# core.net
KiCad netlist of a schematic drawn in EAGLE
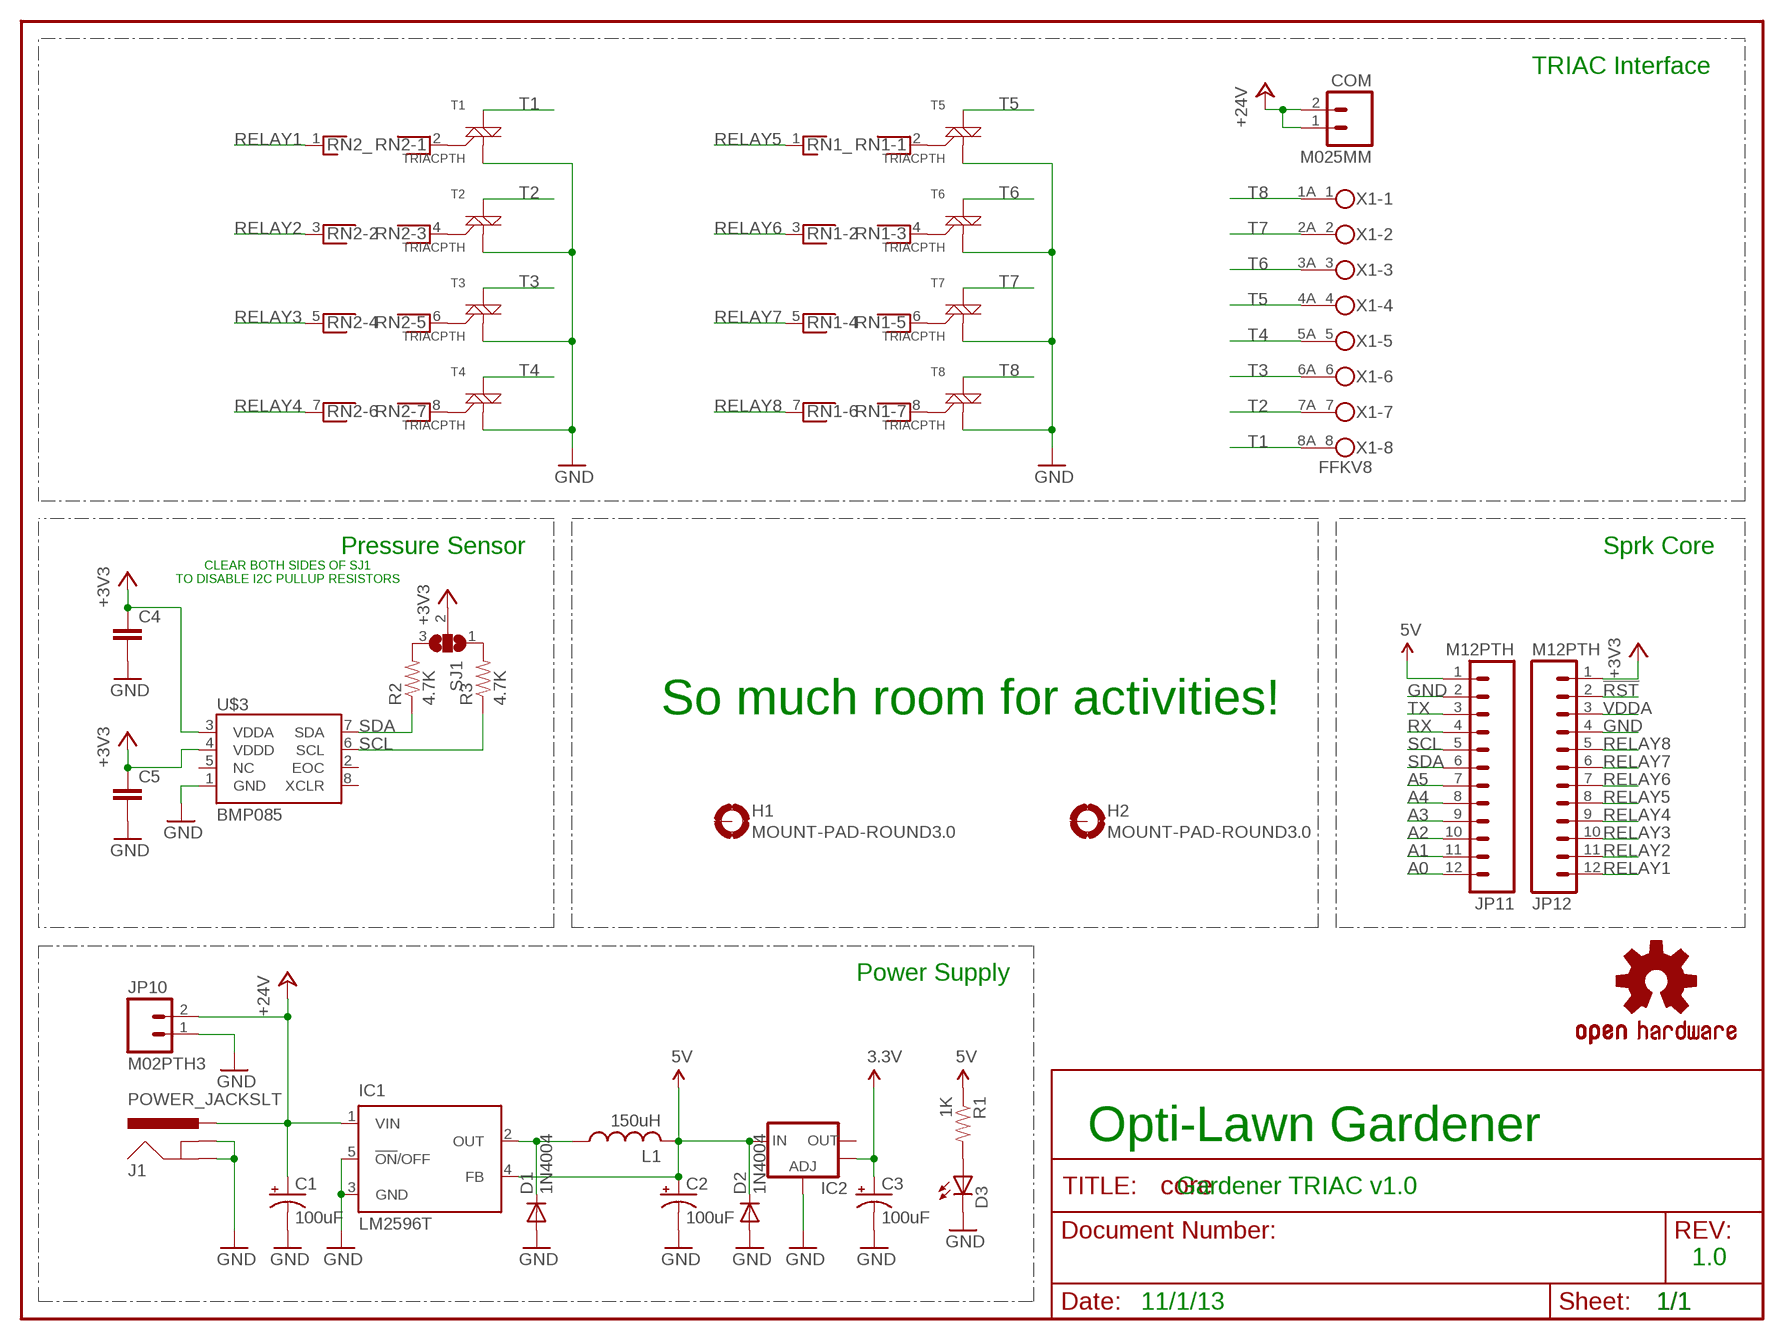
[diagram p0: schematic, sheet 1]

(export (version "E")
  (design (tool "Eeschema 10.0.6"))
  (components
    (comp (ref "C1")
      (value "100uF")
      (footprint "eagle-import:CPOL-RADIAL-100UF-25V")
      (fields (field (name "MPN") "10NA100MEFC6.3X11"))
      (libsource (lib "eagle-import") (part "CAP_POLPTH1"))
    )
    (comp (ref "C2")
      (value "100uF")
      (footprint "eagle-import:CPOL-RADIAL-100UF-25V")
      (fields (field (name "MPN") "10NA100MEFC6.3X11"))
      (libsource (lib "eagle-import") (part "CAP_POLPTH1"))
    )
    (comp (ref "C3")
      (value "100uF")
      (footprint "eagle-import:CPOL-RADIAL-100UF-25V")
      (fields (field (name "MPN") "10NA100MEFC6.3X11"))
      (libsource (lib "eagle-import") (part "CAP_POLPTH1"))
    )
    (comp (ref "C4")
      (value "CAP0402-CAP")
      (footprint "eagle-import:0402-CAP")
      (libsource (lib "eagle-import") (part "CAP0402-CAP"))
    )
    (comp (ref "C5")
      (value "CAP0402-CAP")
      (footprint "eagle-import:0402-CAP")
      (libsource (lib "eagle-import") (part "CAP0402-CAP"))
    )
    (comp (ref "COM")
      (value "M025MM")
      (footprint "eagle-import:SCREWTERMINAL-5MM-2")
      (fields (field (name "MPN") "724"))
      (libsource (lib "eagle-import") (part "M025MM"))
    )
    (comp (ref "D1")
      (value "1N4004")
      (footprint "eagle-import:DO41-10")
      (fields (field (name "MF") "FAIRCHILD SEMICONDUCTOR"))
      (libsource (lib "eagle-import") (part "1N4004"))
    )
    (comp (ref "D2")
      (value "1N4004")
      (footprint "eagle-import:DO41-10")
      (fields (field (name "MF") "FAIRCHILD SEMICONDUCTOR"))
      (libsource (lib "eagle-import") (part "1N4004"))
    )
    (comp (ref "D3")
      (value "LED3MM")
      (footprint "eagle-import:LED3MM")
      (fields (field (name "MPN") "L-710A8CB/1GD"))
      (libsource (lib "eagle-import") (part "LED3MM"))
    )
    (comp (ref "H1")
      (value "MOUNT-PAD-ROUND3.0")
      (footprint "eagle-import:3,0-PAD")
      (libsource (lib "eagle-import") (part "MOUNT-PAD-ROUND3.0"))
    )
    (comp (ref "H2")
      (value "MOUNT-PAD-ROUND3.0")
      (footprint "eagle-import:3,0-PAD")
      (libsource (lib "eagle-import") (part "MOUNT-PAD-ROUND3.0"))
    )
    (comp (ref "IC1")
      (value "LM2596T")
      (footprint "eagle-import:T05D")
      (fields
        (field (name "MPN") "LM2596T-ADJ/LF02")
        (field (name "MF") "NATIONAL SEMICONDUCTOR")
        (field (name "MPN_1") "LM2596T-5.0/NOPB")
        (field (name "OC_NEWARK") "41K3851")
      )
      (libsource (lib "eagle-import") (part "LM2596T"))
    )
    (comp (ref "IC2")
      (value "V_REG_LM1117SOT223")
      (footprint "eagle-import:SOT223")
      (fields (field (name "MPN") "LM1117MPX-3.3/NOPB"))
      (libsource (lib "eagle-import") (part "V_REG_LM1117SOT223"))
    )
    (comp (ref "J1")
      (value "POWER_JACKSLT")
      (footprint "eagle-import:POWER_JACK_SLOT")
      (libsource (lib "eagle-import") (part "POWER_JACKSLT"))
    )
    (comp (ref "JP10")
      (value "M02PTH3")
      (footprint "eagle-import:1X02_LONGPADS")
      (libsource (lib "eagle-import") (part "M02PTH3"))
    )
    (comp (ref "JP11")
      (value "M12PTH")
      (footprint "eagle-import:1X12-SMALL-PADS")
      (libsource (lib "eagle-import") (part "M12PTH"))
    )
    (comp (ref "JP12")
      (value "M12PTH")
      (footprint "eagle-import:1X12-SMALL-PADS")
      (libsource (lib "eagle-import") (part "M12PTH"))
    )
    (comp (ref "L1")
      (value "150uH")
      (footprint "eagle-import:6000")
      (fields (field (name "MPN") "RLB9012-151KL"))
      (libsource (lib "eagle-import") (part "L"))
    )
    (comp (ref "LOGO2")
      (value "OSHW-LOGOL")
      (footprint "eagle-import:OSHW-LOGO-L")
      (libsource (lib "eagle-import") (part "OSHW-LOGOL"))
    )
    (comp (ref "R1")
      (value "1K")
      (footprint "eagle-import:AXIAL-0.3")
      (fields (field (name "MF") "FARNELL") (field (name "MPN") "MCF 1W 1K"))
      (libsource (lib "eagle-import") (part "RESISTORAXIAL-0.3"))
    )
    (comp (ref "R2")
      (value "4.7K")
      (footprint "eagle-import:AXIAL-0.3")
      (fields (field (name "MF") "FARNELL") (field (name "MPN") "MF25 4K7"))
      (libsource (lib "eagle-import") (part "RESISTORAXIAL-0.3"))
    )
    (comp (ref "R3")
      (value "4.7K")
      (footprint "eagle-import:AXIAL-0.3")
      (fields (field (name "MF") "FARNELL") (field (name "MPN") "MF25 4K7"))
      (libsource (lib "eagle-import") (part "RESISTORAXIAL-0.3"))
    )
    (comp (ref "RN1")
      (value "RNX7")
      (footprint "eagle-import:RN-8")
      (fields (field (name "MPN") "CSC09A01330RGEK") (field (name "OC_NEWARK") "71M1507"))
      (libsource (lib "eagle-import") (part "RNX7"))
    )
    (comp (ref "RN2")
      (value "RNX7")
      (footprint "eagle-import:RN-8")
      (fields (field (name "MPN") "CSC09A01330RGEK") (field (name "OC_NEWARK") "71M1507"))
      (libsource (lib "eagle-import") (part "RNX7"))
    )
    (comp (ref "SJ1")
      (value "SJ2W")
      (footprint "eagle-import:SJ_2")
      (libsource (lib "eagle-import") (part "SJ2W"))
    )
    (comp (ref "T1")
      (value "TRIACPTH")
      (footprint "eagle-import:TO-92")
      (fields (field (name "MF") "ON SEMICONDUCTOR") (field (name "MPN") "MAC97A6G"))
      (libsource (lib "eagle-import") (part "TRIACPTH"))
    )
    (comp (ref "T2")
      (value "TRIACPTH")
      (footprint "eagle-import:TO-92")
      (fields (field (name "MF") "ON SEMICONDUCTOR") (field (name "MPN") "MAC97A6G"))
      (libsource (lib "eagle-import") (part "TRIACPTH"))
    )
    (comp (ref "T3")
      (value "TRIACPTH")
      (footprint "eagle-import:TO-92")
      (fields (field (name "MF") "ON SEMICONDUCTOR") (field (name "MPN") "MAC97A6G"))
      (libsource (lib "eagle-import") (part "TRIACPTH"))
    )
    (comp (ref "T4")
      (value "TRIACPTH")
      (footprint "eagle-import:TO-92")
      (fields (field (name "MF") "ON SEMICONDUCTOR") (field (name "MPN") "MAC97A6G"))
      (libsource (lib "eagle-import") (part "TRIACPTH"))
    )
    (comp (ref "T5")
      (value "TRIACPTH")
      (footprint "eagle-import:TO-92")
      (fields (field (name "MF") "ON SEMICONDUCTOR") (field (name "MPN") "MAC97A6G"))
      (libsource (lib "eagle-import") (part "TRIACPTH"))
    )
    (comp (ref "T6")
      (value "TRIACPTH")
      (footprint "eagle-import:TO-92")
      (fields (field (name "MF") "ON SEMICONDUCTOR") (field (name "MPN") "MAC97A6G"))
      (libsource (lib "eagle-import") (part "TRIACPTH"))
    )
    (comp (ref "T7")
      (value "TRIACPTH")
      (footprint "eagle-import:TO-92")
      (fields (field (name "MF") "ON SEMICONDUCTOR") (field (name "MPN") "MAC97A6G"))
      (libsource (lib "eagle-import") (part "TRIACPTH"))
    )
    (comp (ref "T8")
      (value "TRIACPTH")
      (footprint "eagle-import:TO-92")
      (fields (field (name "MF") "ON SEMICONDUCTOR") (field (name "MPN") "MAC97A6G"))
      (libsource (lib "eagle-import") (part "TRIACPTH"))
    )
    (comp (ref "U$3")
      (value "BMP085")
      (footprint "eagle-import:BMP085")
      (libsource (lib "eagle-import") (part "BMP085"))
    )
    (comp (ref "X1")
      (value "FFKV8")
      (footprint "eagle-import:FFKV8")
      (libsource (lib "eagle-import") (part "FFKV8"))
    )
  )
  (nets
    (net (code "1") (name "+3V3") (class "Default")
      (node (ref "C4") (pin "1") (pinfunction "1_1") (pintype "passive"))
      (node (ref "C5") (pin "1") (pinfunction "1_1") (pintype "passive"))
      (node (ref "JP12") (pin "1") (pinfunction "1_1") (pintype "passive"))
      (node (ref "SJ1") (pin "2") (pinfunction "2_2") (pintype "passive"))
      (node (ref "U$3") (pin "3") (pinfunction "VDDA_3") (pintype "power_in"))
      (node (ref "U$3") (pin "4") (pinfunction "VDDD_4") (pintype "power_in"))
    )
    (net (code "2") (name "+24V") (class "Default")
      (node (ref "C1") (pin "1") (pinfunction "+_1") (pintype "passive"))
      (node (ref "COM") (pin "1") (pinfunction "1_1") (pintype "passive"))
      (node (ref "COM") (pin "2") (pinfunction "2_2") (pintype "passive"))
      (node (ref "IC1") (pin "1") (pinfunction "VIN_1") (pintype "input"))
      (node (ref "J1") (pin "PWR") (pinfunction "PWR_PWR") (pintype "bidirectional"))
      (node (ref "JP10") (pin "2") (pinfunction "2_2") (pintype "passive"))
    )
    (net (code "3") (name "/A0") (class "Default")
      (node (ref "JP11") (pin "12") (pinfunction "12_12") (pintype "passive"))
    )
    (net (code "4") (name "/A1") (class "Default")
      (node (ref "JP11") (pin "11") (pinfunction "11_11") (pintype "passive"))
    )
    (net (code "5") (name "/A2") (class "Default")
      (node (ref "JP11") (pin "10") (pinfunction "10_10") (pintype "passive"))
    )
    (net (code "6") (name "/A3") (class "Default")
      (node (ref "JP11") (pin "9") (pinfunction "9_9") (pintype "passive"))
    )
    (net (code "7") (name "/A4") (class "Default")
      (node (ref "JP11") (pin "8") (pinfunction "8_8") (pintype "passive"))
    )
    (net (code "8") (name "/A5") (class "Default")
      (node (ref "JP11") (pin "7") (pinfunction "7_7") (pintype "passive"))
    )
    (net (code "9") (name "/RELAY1") (class "Default")
      (node (ref "JP12") (pin "12") (pinfunction "12_12") (pintype "passive"))
      (node (ref "RN2") (pin "1") (pinfunction "1_1") (pintype "passive"))
    )
    (net (code "10") (name "/RELAY2") (class "Default")
      (node (ref "JP12") (pin "11") (pinfunction "11_11") (pintype "passive"))
      (node (ref "RN2") (pin "3") (pinfunction "1_3") (pintype "passive"))
    )
    (net (code "11") (name "/RELAY3") (class "Default")
      (node (ref "JP12") (pin "10") (pinfunction "10_10") (pintype "passive"))
      (node (ref "RN2") (pin "5") (pinfunction "1_5") (pintype "passive"))
    )
    (net (code "12") (name "/RELAY4") (class "Default")
      (node (ref "JP12") (pin "9") (pinfunction "9_9") (pintype "passive"))
      (node (ref "RN2") (pin "7") (pinfunction "1_7") (pintype "passive"))
    )
    (net (code "13") (name "/RELAY5") (class "Default")
      (node (ref "JP12") (pin "8") (pinfunction "8_8") (pintype "passive"))
      (node (ref "RN1") (pin "1") (pinfunction "1_1") (pintype "passive"))
    )
    (net (code "14") (name "/RELAY6") (class "Default")
      (node (ref "JP12") (pin "7") (pinfunction "7_7") (pintype "passive"))
      (node (ref "RN1") (pin "3") (pinfunction "1_3") (pintype "passive"))
    )
    (net (code "15") (name "/RELAY7") (class "Default")
      (node (ref "JP12") (pin "6") (pinfunction "6_6") (pintype "passive"))
      (node (ref "RN1") (pin "5") (pinfunction "1_5") (pintype "passive"))
    )
    (net (code "16") (name "/RELAY8") (class "Default")
      (node (ref "JP12") (pin "5") (pinfunction "5_5") (pintype "passive"))
      (node (ref "RN1") (pin "7") (pinfunction "1_7") (pintype "passive"))
    )
    (net (code "17") (name "/RX") (class "Default")
      (node (ref "JP11") (pin "4") (pinfunction "4_4") (pintype "passive"))
    )
    (net (code "18") (name "/SCL") (class "Default")
      (node (ref "JP11") (pin "5") (pinfunction "5_5") (pintype "passive"))
      (node (ref "R3") (pin "P$1") (pinfunction "1_P$1") (pintype "passive"))
      (node (ref "U$3") (pin "6") (pinfunction "SCL_6") (pintype "input"))
    )
    (net (code "19") (name "/SDA") (class "Default")
      (node (ref "JP11") (pin "6") (pinfunction "6_6") (pintype "passive"))
      (node (ref "R2") (pin "P$1") (pinfunction "1_P$1") (pintype "passive"))
      (node (ref "U$3") (pin "7") (pinfunction "SDA_7") (pintype "bidirectional"))
    )
    (net (code "20") (name "/T1") (class "Default")
      (node (ref "T1") (pin "3") (pinfunction "M2_3") (pintype "bidirectional"))
      (node (ref "X1") (pin "8A") (pinfunction "2_8A") (pintype "passive"))
    )
    (net (code "21") (name "/T2") (class "Default")
      (node (ref "T2") (pin "3") (pinfunction "M2_3") (pintype "bidirectional"))
      (node (ref "X1") (pin "7A") (pinfunction "2_7A") (pintype "passive"))
    )
    (net (code "22") (name "/T3") (class "Default")
      (node (ref "T3") (pin "3") (pinfunction "M2_3") (pintype "bidirectional"))
      (node (ref "X1") (pin "6A") (pinfunction "2_6A") (pintype "passive"))
    )
    (net (code "23") (name "/T4") (class "Default")
      (node (ref "T4") (pin "3") (pinfunction "M2_3") (pintype "bidirectional"))
      (node (ref "X1") (pin "5A") (pinfunction "2_5A") (pintype "passive"))
    )
    (net (code "24") (name "/T5") (class "Default")
      (node (ref "T5") (pin "3") (pinfunction "M2_3") (pintype "bidirectional"))
      (node (ref "X1") (pin "4A") (pinfunction "2_4A") (pintype "passive"))
    )
    (net (code "25") (name "/T6") (class "Default")
      (node (ref "T6") (pin "3") (pinfunction "M2_3") (pintype "bidirectional"))
      (node (ref "X1") (pin "3A") (pinfunction "2_3A") (pintype "passive"))
    )
    (net (code "26") (name "/T7") (class "Default")
      (node (ref "T7") (pin "3") (pinfunction "M2_3") (pintype "bidirectional"))
      (node (ref "X1") (pin "2A") (pinfunction "2_2A") (pintype "passive"))
    )
    (net (code "27") (name "/T8") (class "Default")
      (node (ref "T8") (pin "3") (pinfunction "M2_3") (pintype "bidirectional"))
      (node (ref "X1") (pin "1A") (pinfunction "2_1A") (pintype "passive"))
    )
    (net (code "28") (name "/TX") (class "Default")
      (node (ref "JP11") (pin "3") (pinfunction "3_3") (pintype "passive"))
    )
    (net (code "29") (name "/VDDA") (class "Default")
      (node (ref "JP12") (pin "3") (pinfunction "3_3") (pintype "passive"))
    )
    (net (code "30") (name "/~{RST}") (class "Default")
      (node (ref "JP12") (pin "2") (pinfunction "2_2") (pintype "passive"))
    )
    (net (code "31") (name "3.3V") (class "Default")
      (node (ref "C3") (pin "1") (pinfunction "+_1") (pintype "passive"))
      (node (ref "IC2") (pin "4") (pinfunction "OUT_4") (pintype "output"))
    )
    (net (code "32") (name "5V") (class "Default")
      (node (ref "C2") (pin "1") (pinfunction "+_1") (pintype "passive"))
      (node (ref "D2") (pin "C") (pinfunction "C_C") (pintype "passive"))
      (node (ref "IC1") (pin "4") (pinfunction "FB_4") (pintype "input"))
      (node (ref "IC2") (pin "3") (pinfunction "IN_3") (pintype "input"))
      (node (ref "JP11") (pin "1") (pinfunction "1_1") (pintype "passive"))
      (node (ref "L1") (pin "2") (pinfunction "2_2") (pintype "passive"))
      (node (ref "R1") (pin "P$1") (pinfunction "1_P$1") (pintype "passive"))
    )
    (net (code "33") (name "GND") (class "Default")
      (node (ref "C1") (pin "2") (pinfunction "-_2") (pintype "passive"))
      (node (ref "C2") (pin "2") (pinfunction "-_2") (pintype "passive"))
      (node (ref "C3") (pin "2") (pinfunction "-_2") (pintype "passive"))
      (node (ref "C4") (pin "2") (pinfunction "2_2") (pintype "passive"))
      (node (ref "C5") (pin "2") (pinfunction "2_2") (pintype "passive"))
      (node (ref "D1") (pin "A") (pinfunction "A_A") (pintype "passive"))
      (node (ref "D2") (pin "A") (pinfunction "A_A") (pintype "passive"))
      (node (ref "D3") (pin "K") (pinfunction "C_K") (pintype "passive"))
      (node (ref "IC1") (pin "3") (pinfunction "GND_3") (pintype "power_in"))
      (node (ref "IC1") (pin "5") (pinfunction "~{ON}/OFF_5") (pintype "input"))
      (node (ref "IC2") (pin "1") (pinfunction "ADJ_1") (pintype "input"))
      (node (ref "J1") (pin "GND@1") (pinfunction "GNDBREAK_GND@1") (pintype "bidirectional"))
      (node (ref "J1") (pin "GND@2") (pinfunction "GND_GND@2") (pintype "bidirectional"))
      (node (ref "JP10") (pin "1") (pinfunction "1_1") (pintype "passive"))
      (node (ref "JP11") (pin "2") (pinfunction "2_2") (pintype "passive"))
      (node (ref "JP12") (pin "4") (pinfunction "4_4") (pintype "passive"))
      (node (ref "T1") (pin "1") (pinfunction "M1_1") (pintype "bidirectional"))
      (node (ref "T2") (pin "1") (pinfunction "M1_1") (pintype "bidirectional"))
      (node (ref "T3") (pin "1") (pinfunction "M1_1") (pintype "bidirectional"))
      (node (ref "T4") (pin "1") (pinfunction "M1_1") (pintype "bidirectional"))
      (node (ref "T5") (pin "1") (pinfunction "M1_1") (pintype "bidirectional"))
      (node (ref "T6") (pin "1") (pinfunction "M1_1") (pintype "bidirectional"))
      (node (ref "T7") (pin "1") (pinfunction "M1_1") (pintype "bidirectional"))
      (node (ref "T8") (pin "1") (pinfunction "M1_1") (pintype "bidirectional"))
      (node (ref "U$3") (pin "1") (pinfunction "GND_1") (pintype "power_in"))
    )
    (net (code "34") (name "Net-(IC1-OUT)") (class "Default")
      (node (ref "D1") (pin "C") (pinfunction "C_C") (pintype "passive"))
      (node (ref "IC1") (pin "2") (pinfunction "OUT_2") (pintype "output"))
      (node (ref "L1") (pin "1") (pinfunction "1_1") (pintype "passive"))
    )
    (net (code "35") (name "Net-(R1-2)") (class "Default")
      (node (ref "D3") (pin "A") (pinfunction "A_A") (pintype "passive"))
      (node (ref "R1") (pin "P$2") (pinfunction "2_P$2") (pintype "passive"))
    )
    (net (code "36") (name "Net-(R2-2)") (class "Default")
      (node (ref "R2") (pin "P$2") (pinfunction "2_P$2") (pintype "passive"))
      (node (ref "SJ1") (pin "3") (pinfunction "3_3") (pintype "passive"))
    )
    (net (code "37") (name "Net-(R3-2)") (class "Default")
      (node (ref "R3") (pin "P$2") (pinfunction "2_P$2") (pintype "passive"))
      (node (ref "SJ1") (pin "1") (pinfunction "1_1") (pintype "passive"))
    )
    (net (code "38") (name "Net-(RN1A-1)") (class "Default")
      (node (ref "RN1") (pin "2") (pinfunction "1_2") (pintype "passive"))
      (node (ref "T5") (pin "2") (pinfunction "G_2") (pintype "bidirectional"))
    )
    (net (code "39") (name "Net-(RN1C-1)") (class "Default")
      (node (ref "RN1") (pin "4") (pinfunction "1_4") (pintype "passive"))
      (node (ref "T6") (pin "2") (pinfunction "G_2") (pintype "bidirectional"))
    )
    (net (code "40") (name "Net-(RN1E-1)") (class "Default")
      (node (ref "RN1") (pin "6") (pinfunction "1_6") (pintype "passive"))
      (node (ref "T7") (pin "2") (pinfunction "G_2") (pintype "bidirectional"))
    )
    (net (code "41") (name "Net-(RN1G-1)") (class "Default")
      (node (ref "RN1") (pin "8") (pinfunction "1_8") (pintype "passive"))
      (node (ref "T8") (pin "2") (pinfunction "G_2") (pintype "bidirectional"))
    )
    (net (code "42") (name "Net-(RN2A-1)") (class "Default")
      (node (ref "RN2") (pin "2") (pinfunction "1_2") (pintype "passive"))
      (node (ref "T1") (pin "2") (pinfunction "G_2") (pintype "bidirectional"))
    )
    (net (code "43") (name "Net-(RN2C-1)") (class "Default")
      (node (ref "RN2") (pin "4") (pinfunction "1_4") (pintype "passive"))
      (node (ref "T2") (pin "2") (pinfunction "G_2") (pintype "bidirectional"))
    )
    (net (code "44") (name "Net-(RN2E-1)") (class "Default")
      (node (ref "RN2") (pin "6") (pinfunction "1_6") (pintype "passive"))
      (node (ref "T3") (pin "2") (pinfunction "G_2") (pintype "bidirectional"))
    )
    (net (code "45") (name "Net-(RN2G-1)") (class "Default")
      (node (ref "RN2") (pin "8") (pinfunction "1_8") (pintype "passive"))
      (node (ref "T4") (pin "2") (pinfunction "G_2") (pintype "bidirectional"))
    )
    (net (code "46") (name "unconnected-(H1-MOUNT-PadB3,0)") (class "Default")
      (node (ref "H1") (pin "B3,0") (pinfunction "MOUNT_B3,0") (pintype "passive"))
    )
    (net (code "47") (name "unconnected-(H2-MOUNT-PadB3,0)") (class "Default")
      (node (ref "H2") (pin "B3,0") (pinfunction "MOUNT_B3,0") (pintype "passive"))
    )
    (net (code "48") (name "unconnected-(IC2-OUT-Pad2)") (class "Default")
      (node (ref "IC2") (pin "2") (pinfunction "OUT_2") (pintype "output"))
    )
    (net (code "49") (name "unconnected-(U$3-EOC-Pad2)") (class "Default")
      (node (ref "U$3") (pin "2") (pinfunction "EOC_2") (pintype "output"))
    )
    (net (code "50") (name "unconnected-(U$3-NC-Pad5)") (class "Default")
      (node (ref "U$3") (pin "5") (pinfunction "NC_5") (pintype "bidirectional"))
    )
    (net (code "51") (name "unconnected-(U$3-XCLR-Pad8)") (class "Default")
      (node (ref "U$3") (pin "8") (pinfunction "XCLR_8") (pintype "input"))
    )
    (net (code "52") (name "unconnected-(X1-Pad1)") (class "Default")
      (node (ref "X1") (pin "1") (pinfunction "1_1") (pintype "passive"))
    )
    (net (code "53") (name "unconnected-(X1B-1-Pad2)") (class "Default")
      (node (ref "X1") (pin "2") (pinfunction "1_2") (pintype "passive"))
    )
    (net (code "54") (name "unconnected-(X1C-1-Pad3)") (class "Default")
      (node (ref "X1") (pin "3") (pinfunction "1_3") (pintype "passive"))
    )
    (net (code "55") (name "unconnected-(X1D-1-Pad4)") (class "Default")
      (node (ref "X1") (pin "4") (pinfunction "1_4") (pintype "passive"))
    )
    (net (code "56") (name "unconnected-(X1E-1-Pad5)") (class "Default")
      (node (ref "X1") (pin "5") (pinfunction "1_5") (pintype "passive"))
    )
    (net (code "57") (name "unconnected-(X1F-1-Pad6)") (class "Default")
      (node (ref "X1") (pin "6") (pinfunction "1_6") (pintype "passive"))
    )
    (net (code "58") (name "unconnected-(X1G-1-Pad7)") (class "Default")
      (node (ref "X1") (pin "7") (pinfunction "1_7") (pintype "passive"))
    )
    (net (code "59") (name "unconnected-(X1H-1-Pad8)") (class "Default")
      (node (ref "X1") (pin "8") (pinfunction "1_8") (pintype "passive"))
    )
  )
)
